# Power-board-new-version.net
KiCad netlist of a schematic drawn in EAGLE
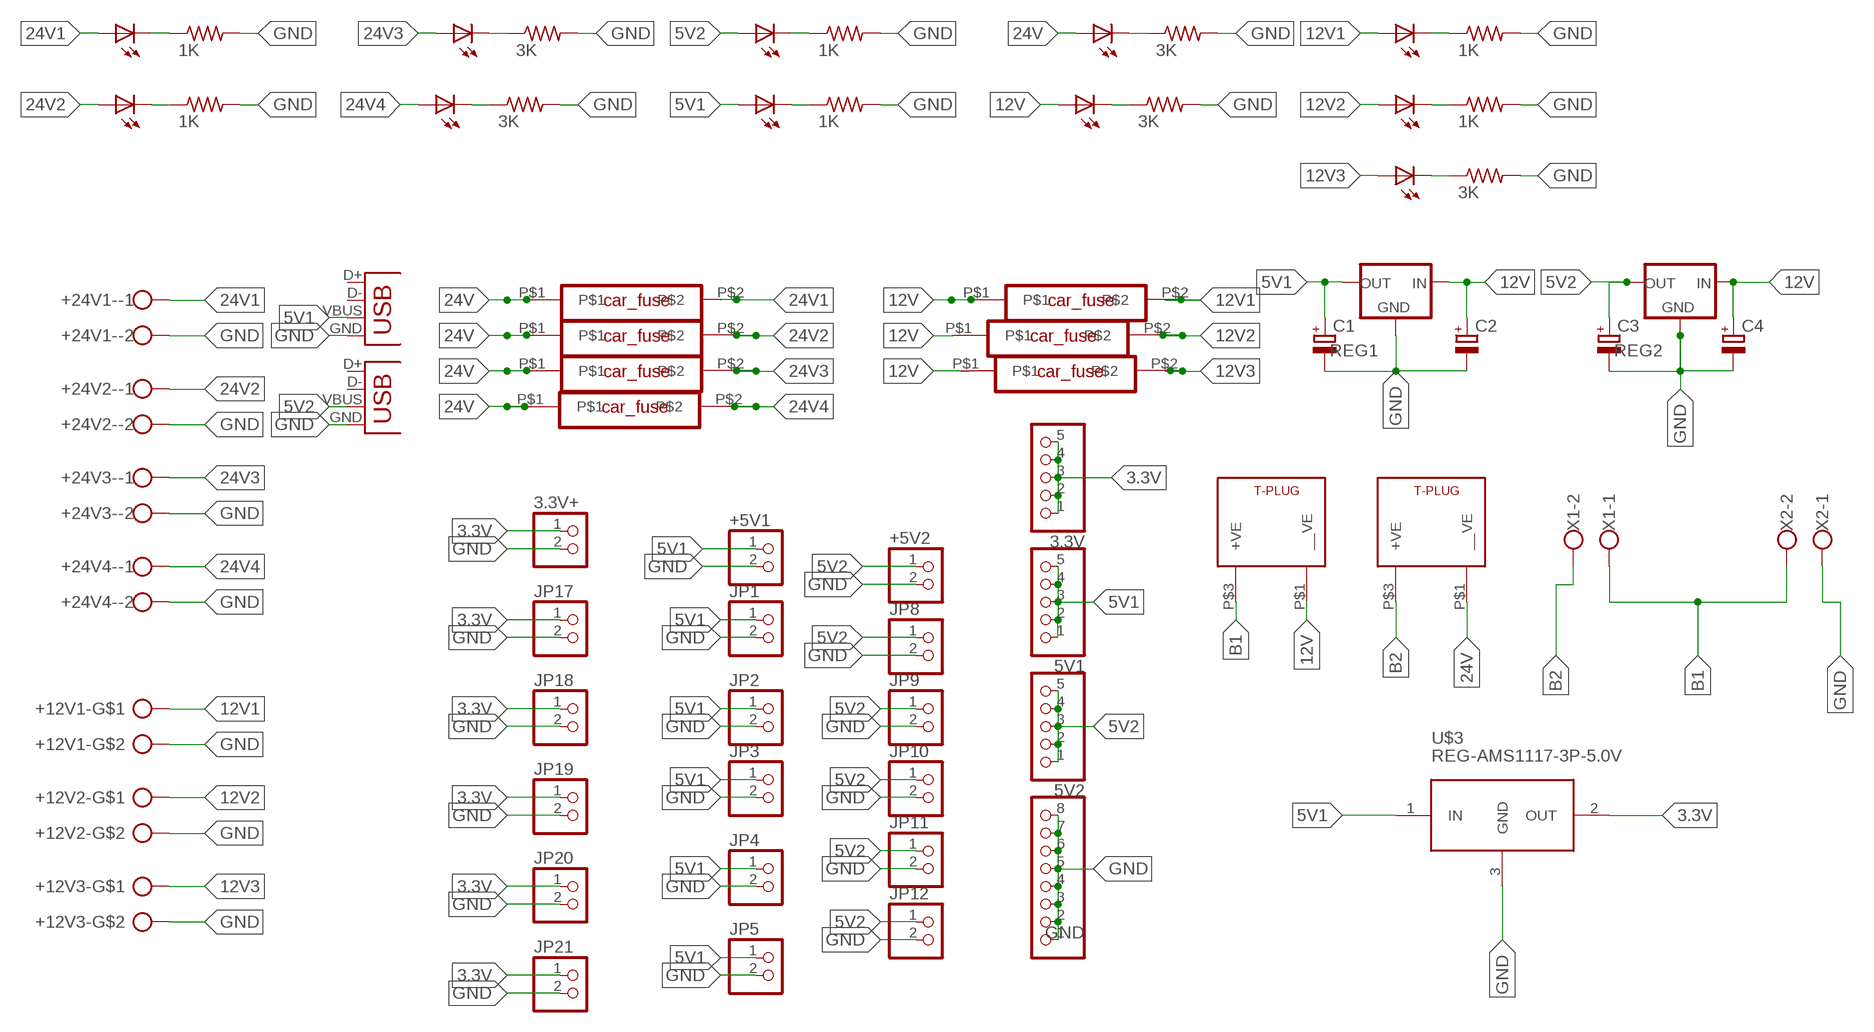
[diagram p0: schematic, sheet 1]

(export (version "E")
  (design (tool "Eeschema 10.0.6"))
  (components
    (comp (ref "+5V1")
      (value "PINHD-2_DATA")
      (footprint "eagle-import:1X02_DATA")
      (libsource (lib "eagle-import") (part "PINHD-2_DATA"))
    )
    (comp (ref "+5V2")
      (value "PINHD-2_DATA")
      (footprint "eagle-import:1X02_DATA")
      (libsource (lib "eagle-import") (part "PINHD-2_DATA"))
    )
    (comp (ref "+12V1-")
      (value "CON_PTR_2")
      (footprint "eagle-import:AK300_2")
      (libsource (lib "eagle-import") (part "CON_PTR_2"))
    )
    (comp (ref "+12V2-")
      (value "CON_PTR_2")
      (footprint "eagle-import:AK300_2")
      (libsource (lib "eagle-import") (part "CON_PTR_2"))
    )
    (comp (ref "+12V3-")
      (value "CON_PTR_2")
      (footprint "eagle-import:AK300_2")
      (libsource (lib "eagle-import") (part "CON_PTR_2"))
    )
    (comp (ref "+24V1-")
      (value "ROSTA.POWER")
      (footprint "eagle-import:W239-302")
      (libsource (lib "eagle-import") (part "ROSTA.POWER"))
    )
    (comp (ref "+24V2-")
      (value "ROSTA.POWER")
      (footprint "eagle-import:W239-302")
      (libsource (lib "eagle-import") (part "ROSTA.POWER"))
    )
    (comp (ref "+24V3-")
      (value "ROSTA.POWER")
      (footprint "eagle-import:W239-302")
      (libsource (lib "eagle-import") (part "ROSTA.POWER"))
    )
    (comp (ref "+24V4-")
      (value "ROSTA.POWER")
      (footprint "eagle-import:W239-302")
      (libsource (lib "eagle-import") (part "ROSTA.POWER"))
    )
    (comp (ref "1K")
      (value "1K")
      (footprint "eagle-import:0204_7")
      (libsource (lib "eagle-import") (part "RES-7"))
    )
    (comp (ref "1K1")
      (value "1K")
      (footprint "eagle-import:0204_7")
      (libsource (lib "eagle-import") (part "RES-7"))
    )
    (comp (ref "1K2")
      (value "1K")
      (footprint "eagle-import:0204_7")
      (libsource (lib "eagle-import") (part "RES-7"))
    )
    (comp (ref "3.3V")
      (value "PINHD-1X5")
      (footprint "eagle-import:1X05")
      (libsource (lib "eagle-import") (part "PINHD-1X5"))
    )
    (comp (ref "3.3V+")
      (value "PINHD-2_DATA")
      (footprint "eagle-import:1X02_DATA")
      (libsource (lib "eagle-import") (part "PINHD-2_DATA"))
    )
    (comp (ref "5V1")
      (value "PINHD-1X5")
      (footprint "eagle-import:1X05")
      (libsource (lib "eagle-import") (part "PINHD-1X5"))
    )
    (comp (ref "5V2")
      (value "PINHD-1X5")
      (footprint "eagle-import:1X05")
      (libsource (lib "eagle-import") (part "PINHD-1X5"))
    )
    (comp (ref "C1")
      (value "CAP_POL")
      (footprint "eagle-import:E3,5-8")
      (libsource (lib "eagle-import") (part "CAP_POL"))
    )
    (comp (ref "C2")
      (value "CAP_POL")
      (footprint "eagle-import:E3,5-8")
      (libsource (lib "eagle-import") (part "CAP_POL"))
    )
    (comp (ref "C3")
      (value "CAP_POL")
      (footprint "eagle-import:E3,5-8")
      (libsource (lib "eagle-import") (part "CAP_POL"))
    )
    (comp (ref "C4")
      (value "CAP_POL")
      (footprint "eagle-import:E3,5-8")
      (libsource (lib "eagle-import") (part "CAP_POL"))
    )
    (comp (ref "GND")
      (value "PINHD-1X8")
      (footprint "eagle-import:1X08")
      (libsource (lib "eagle-import") (part "PINHD-1X8"))
    )
    (comp (ref "JP1")
      (value "PINHD-2_DATA")
      (footprint "eagle-import:1X02_DATA")
      (libsource (lib "eagle-import") (part "PINHD-2_DATA"))
    )
    (comp (ref "JP2")
      (value "PINHD-2_DATA")
      (footprint "eagle-import:1X02_DATA")
      (libsource (lib "eagle-import") (part "PINHD-2_DATA"))
    )
    (comp (ref "JP3")
      (value "PINHD-2_DATA")
      (footprint "eagle-import:1X02_DATA")
      (libsource (lib "eagle-import") (part "PINHD-2_DATA"))
    )
    (comp (ref "JP4")
      (value "PINHD-2_DATA")
      (footprint "eagle-import:1X02_DATA")
      (libsource (lib "eagle-import") (part "PINHD-2_DATA"))
    )
    (comp (ref "JP5")
      (value "PINHD-2_DATA")
      (footprint "eagle-import:1X02_DATA")
      (libsource (lib "eagle-import") (part "PINHD-2_DATA"))
    )
    (comp (ref "JP8")
      (value "PINHD-2_DATA")
      (footprint "eagle-import:1X02_DATA")
      (libsource (lib "eagle-import") (part "PINHD-2_DATA"))
    )
    (comp (ref "JP9")
      (value "PINHD-2_DATA")
      (footprint "eagle-import:1X02_DATA")
      (libsource (lib "eagle-import") (part "PINHD-2_DATA"))
    )
    (comp (ref "JP10")
      (value "PINHD-2_DATA")
      (footprint "eagle-import:1X02_DATA")
      (libsource (lib "eagle-import") (part "PINHD-2_DATA"))
    )
    (comp (ref "JP11")
      (value "PINHD-2_DATA")
      (footprint "eagle-import:1X02_DATA")
      (libsource (lib "eagle-import") (part "PINHD-2_DATA"))
    )
    (comp (ref "JP12")
      (value "PINHD-2_DATA")
      (footprint "eagle-import:1X02_DATA")
      (libsource (lib "eagle-import") (part "PINHD-2_DATA"))
    )
    (comp (ref "JP17")
      (value "PINHD-2_DATA")
      (footprint "eagle-import:1X02_DATA")
      (libsource (lib "eagle-import") (part "PINHD-2_DATA"))
    )
    (comp (ref "JP18")
      (value "PINHD-2_DATA")
      (footprint "eagle-import:1X02_DATA")
      (libsource (lib "eagle-import") (part "PINHD-2_DATA"))
    )
    (comp (ref "JP19")
      (value "PINHD-2_DATA")
      (footprint "eagle-import:1X02_DATA")
      (libsource (lib "eagle-import") (part "PINHD-2_DATA"))
    )
    (comp (ref "JP20")
      (value "PINHD-2_DATA")
      (footprint "eagle-import:1X02_DATA")
      (libsource (lib "eagle-import") (part "PINHD-2_DATA"))
    )
    (comp (ref "JP21")
      (value "PINHD-2_DATA")
      (footprint "eagle-import:1X02_DATA")
      (libsource (lib "eagle-import") (part "PINHD-2_DATA"))
    )
    (comp (ref "REG1")
      (value "78XX-METAL")
      (footprint "eagle-import:TO3-79")
      (libsource (lib "eagle-import") (part "78XX-METAL"))
    )
    (comp (ref "REG2")
      (value "78XX-METAL")
      (footprint "eagle-import:TO3-79")
      (libsource (lib "eagle-import") (part "78XX-METAL"))
    )
    (comp (ref "U$1")
      (value "LED5V2")
      (footprint "eagle-import:LED3MM")
      (libsource (lib "eagle-import") (part "LED3MM"))
    )
    (comp (ref "U$2")
      (value "LED5V1")
      (footprint "eagle-import:LED3MM")
      (libsource (lib "eagle-import") (part "LED3MM"))
    )
    (comp (ref "U$3")
      (value "REG-AMS1117-3P-5.0V")
      (footprint "eagle-import:REG-AMS1117-3P")
      (libsource (lib "eagle-import") (part "REG-AMS1117-3P-5.0V"))
    )
    (comp (ref "U$4")
      (value "LED24V")
      (footprint "eagle-import:LED3MM")
      (libsource (lib "eagle-import") (part "LED3MM"))
    )
    (comp (ref "U$5")
      (value "T_CONNECTOR")
      (footprint "eagle-import:T-PLUG")
      (libsource (lib "eagle-import") (part "T_CONNECTOR"))
    )
    (comp (ref "U$6")
      (value "T_CONNECTOR")
      (footprint "eagle-import:T-PLUG")
      (libsource (lib "eagle-import") (part "T_CONNECTOR"))
    )
    (comp (ref "U$7")
      (value "1K")
      (footprint "eagle-import:0204_7")
      (libsource (lib "eagle-import") (part "RES-7"))
    )
    (comp (ref "U$8")
      (value "3K")
      (footprint "eagle-import:0204_7")
      (libsource (lib "eagle-import") (part "RES-7"))
    )
    (comp (ref "U$9")
      (value "3K")
      (footprint "eagle-import:0204_7")
      (libsource (lib "eagle-import") (part "RES-7"))
    )
    (comp (ref "U$10")
      (value "CAR_FUSE")
      (footprint "eagle-import:CAR_FUSE")
      (libsource (lib "eagle-import") (part "CAR_FUSE"))
    )
    (comp (ref "U$11")
      (value "CAR_FUSE")
      (footprint "eagle-import:CAR_FUSE")
      (libsource (lib "eagle-import") (part "CAR_FUSE"))
    )
    (comp (ref "U$12")
      (value "CAR_FUSE")
      (footprint "eagle-import:CAR_FUSE")
      (libsource (lib "eagle-import") (part "CAR_FUSE"))
    )
    (comp (ref "U$13")
      (value "CAR_FUSE")
      (footprint "eagle-import:CAR_FUSE")
      (libsource (lib "eagle-import") (part "CAR_FUSE"))
    )
    (comp (ref "U$14")
      (value "CAR_FUSE")
      (footprint "eagle-import:CAR_FUSE")
      (libsource (lib "eagle-import") (part "CAR_FUSE"))
    )
    (comp (ref "U$15")
      (value "CAR_FUSE")
      (footprint "eagle-import:CAR_FUSE")
      (libsource (lib "eagle-import") (part "CAR_FUSE"))
    )
    (comp (ref "U$16")
      (value "CAR_FUSE")
      (footprint "eagle-import:CAR_FUSE")
      (libsource (lib "eagle-import") (part "CAR_FUSE"))
    )
    (comp (ref "U$18")
      (value "LED5V2")
      (footprint "eagle-import:LED3MM")
      (libsource (lib "eagle-import") (part "LED3MM"))
    )
    (comp (ref "U$19")
      (value "LED5V1")
      (footprint "eagle-import:LED3MM")
      (libsource (lib "eagle-import") (part "LED3MM"))
    )
    (comp (ref "U$20")
      (value "LED24V")
      (footprint "eagle-import:LED3MM")
      (libsource (lib "eagle-import") (part "LED3MM"))
    )
    (comp (ref "U$21")
      (value "LED12V")
      (footprint "eagle-import:LED3MM")
      (libsource (lib "eagle-import") (part "LED3MM"))
    )
    (comp (ref "U$22")
      (value "1K")
      (footprint "eagle-import:0204_7")
      (libsource (lib "eagle-import") (part "RES-7"))
    )
    (comp (ref "U$23")
      (value "3K")
      (footprint "eagle-import:0204_7")
      (libsource (lib "eagle-import") (part "RES-7"))
    )
    (comp (ref "U$24")
      (value "3K")
      (footprint "eagle-import:0204_7")
      (libsource (lib "eagle-import") (part "RES-7"))
    )
    (comp (ref "U$25")
      (value "LED5V2")
      (footprint "eagle-import:LED3MM")
      (libsource (lib "eagle-import") (part "LED3MM"))
    )
    (comp (ref "U$26")
      (value "LED5V1")
      (footprint "eagle-import:LED3MM")
      (libsource (lib "eagle-import") (part "LED3MM"))
    )
    (comp (ref "U$27")
      (value "LED24V")
      (footprint "eagle-import:LED3MM")
      (libsource (lib "eagle-import") (part "LED3MM"))
    )
    (comp (ref "U$28")
      (value "LED24V")
      (footprint "eagle-import:LED3MM")
      (libsource (lib "eagle-import") (part "LED3MM"))
    )
    (comp (ref "U$29")
      (value "1K")
      (footprint "eagle-import:0204_7")
      (libsource (lib "eagle-import") (part "RES-7"))
    )
    (comp (ref "U$31")
      (value "3K")
      (footprint "eagle-import:0204_7")
      (libsource (lib "eagle-import") (part "RES-7"))
    )
    (comp (ref "USB1")
      (value "USB-A-H")
      (footprint "eagle-import:USB-A-H")
      (libsource (lib "eagle-import") (part "USB-A-H"))
    )
    (comp (ref "USB2")
      (value "USB-A-H")
      (footprint "eagle-import:USB-A-H")
      (libsource (lib "eagle-import") (part "USB-A-H"))
    )
    (comp (ref "X1")
      (value "ROSTA.POWER")
      (footprint "eagle-import:W239-302")
      (libsource (lib "eagle-import") (part "MIA_LIBRARY-2-2-2_16672108_ROSTA.POWER"))
    )
    (comp (ref "X2")
      (value "ROSTA.POWER")
      (footprint "eagle-import:W239-302")
      (libsource (lib "eagle-import") (part "MIA_LIBRARY-2-2-2_16672108_ROSTA.POWER"))
    )
  )
  (nets
    (net (code "1") (name "3.3V") (class "Default")
      (node (ref "3.3V") (pin "1") (pinfunction "1_1") (pintype "passive"))
      (node (ref "3.3V") (pin "2") (pinfunction "2_2") (pintype "passive"))
      (node (ref "3.3V") (pin "3") (pinfunction "3_3") (pintype "passive"))
      (node (ref "3.3V") (pin "4") (pinfunction "4_4") (pintype "passive"))
      (node (ref "3.3V") (pin "5") (pinfunction "5_5") (pintype "passive"))
      (node (ref "3.3V+") (pin "1") (pinfunction "1_1") (pintype "passive"))
      (node (ref "JP17") (pin "1") (pinfunction "1_1") (pintype "passive"))
      (node (ref "JP18") (pin "1") (pinfunction "1_1") (pintype "passive"))
      (node (ref "JP19") (pin "1") (pinfunction "1_1") (pintype "passive"))
      (node (ref "JP20") (pin "1") (pinfunction "1_1") (pintype "passive"))
      (node (ref "JP21") (pin "1") (pinfunction "1_1") (pintype "passive"))
      (node (ref "U$3") (pin "2") (pinfunction "OUT_2") (pintype "bidirectional"))
    )
    (net (code "2") (name "5V1") (class "Default")
      (node (ref "+5V1") (pin "1") (pinfunction "1_1") (pintype "passive"))
      (node (ref "5V1") (pin "1") (pinfunction "1_1") (pintype "passive"))
      (node (ref "5V1") (pin "2") (pinfunction "2_2") (pintype "passive"))
      (node (ref "5V1") (pin "3") (pinfunction "3_3") (pintype "passive"))
      (node (ref "5V1") (pin "4") (pinfunction "4_4") (pintype "passive"))
      (node (ref "5V1") (pin "5") (pinfunction "5_5") (pintype "passive"))
      (node (ref "C1") (pin "+") (pinfunction "+_+") (pintype "passive"))
      (node (ref "JP1") (pin "1") (pinfunction "1_1") (pintype "passive"))
      (node (ref "JP2") (pin "1") (pinfunction "1_1") (pintype "passive"))
      (node (ref "JP3") (pin "1") (pinfunction "1_1") (pintype "passive"))
      (node (ref "JP4") (pin "1") (pinfunction "1_1") (pintype "passive"))
      (node (ref "JP5") (pin "1") (pinfunction "1_1") (pintype "passive"))
      (node (ref "REG1") (pin "1") (pinfunction "OUT_1") (pintype "passive"))
      (node (ref "U$2") (pin "A") (pinfunction "A_A") (pintype "passive"))
      (node (ref "U$3") (pin "1") (pinfunction "IN_1") (pintype "bidirectional"))
      (node (ref "USB1") (pin "VBUS") (pinfunction "VBUS_VBUS") (pintype "bidirectional"))
    )
    (net (code "3") (name "5V2") (class "Default")
      (node (ref "+5V2") (pin "1") (pinfunction "1_1") (pintype "passive"))
      (node (ref "5V2") (pin "1") (pinfunction "1_1") (pintype "passive"))
      (node (ref "5V2") (pin "2") (pinfunction "2_2") (pintype "passive"))
      (node (ref "5V2") (pin "3") (pinfunction "3_3") (pintype "passive"))
      (node (ref "5V2") (pin "4") (pinfunction "4_4") (pintype "passive"))
      (node (ref "5V2") (pin "5") (pinfunction "5_5") (pintype "passive"))
      (node (ref "C3") (pin "+") (pinfunction "+_+") (pintype "passive"))
      (node (ref "JP10") (pin "1") (pinfunction "1_1") (pintype "passive"))
      (node (ref "JP11") (pin "1") (pinfunction "1_1") (pintype "passive"))
      (node (ref "JP12") (pin "1") (pinfunction "1_1") (pintype "passive"))
      (node (ref "JP8") (pin "1") (pinfunction "1_1") (pintype "passive"))
      (node (ref "JP9") (pin "1") (pinfunction "1_1") (pintype "passive"))
      (node (ref "REG2") (pin "1") (pinfunction "OUT_1") (pintype "passive"))
      (node (ref "U$1") (pin "A") (pinfunction "A_A") (pintype "passive"))
      (node (ref "USB2") (pin "VBUS") (pinfunction "VBUS_VBUS") (pintype "bidirectional"))
    )
    (net (code "4") (name "12V") (class "Default")
      (node (ref "C2") (pin "+") (pinfunction "+_+") (pintype "passive"))
      (node (ref "C4") (pin "+") (pinfunction "+_+") (pintype "passive"))
      (node (ref "REG1") (pin "3") (pinfunction "IN_3") (pintype "input"))
      (node (ref "REG2") (pin "3") (pinfunction "IN_3") (pintype "input"))
      (node (ref "U$14") (pin "P$1") (pinfunction "P$1_P$1") (pintype "bidirectional"))
      (node (ref "U$15") (pin "P$1") (pinfunction "P$1_P$1") (pintype "bidirectional"))
      (node (ref "U$16") (pin "P$1") (pinfunction "P$1_P$1") (pintype "bidirectional"))
      (node (ref "U$28") (pin "A") (pinfunction "A_A") (pintype "passive"))
      (node (ref "U$5") (pin "P$1") (pinfunction "__VE_P$1") (pintype "bidirectional"))
    )
    (net (code "5") (name "12V1") (class "Default")
      (node (ref "+12V1-") (pin "1") (pinfunction "KL_1") (pintype "passive"))
      (node (ref "U$14") (pin "P$2") (pinfunction "P$2_P$2") (pintype "bidirectional"))
      (node (ref "U$25") (pin "A") (pinfunction "A_A") (pintype "passive"))
    )
    (net (code "6") (name "12V2") (class "Default")
      (node (ref "+12V2-") (pin "1") (pinfunction "KL_1") (pintype "passive"))
      (node (ref "U$15") (pin "P$2") (pinfunction "P$2_P$2") (pintype "bidirectional"))
      (node (ref "U$26") (pin "A") (pinfunction "A_A") (pintype "passive"))
    )
    (net (code "7") (name "12V3") (class "Default")
      (node (ref "+12V3-") (pin "1") (pinfunction "KL_1") (pintype "passive"))
      (node (ref "U$16") (pin "P$2") (pinfunction "P$2_P$2") (pintype "bidirectional"))
      (node (ref "U$27") (pin "A") (pinfunction "A_A") (pintype "passive"))
    )
    (net (code "8") (name "24V") (class "Default")
      (node (ref "U$10") (pin "P$1") (pinfunction "P$1_P$1") (pintype "bidirectional"))
      (node (ref "U$11") (pin "P$1") (pinfunction "P$1_P$1") (pintype "bidirectional"))
      (node (ref "U$12") (pin "P$1") (pinfunction "P$1_P$1") (pintype "bidirectional"))
      (node (ref "U$13") (pin "P$1") (pinfunction "P$1_P$1") (pintype "bidirectional"))
      (node (ref "U$4") (pin "A") (pinfunction "A_A") (pintype "passive"))
      (node (ref "U$6") (pin "P$1") (pinfunction "__VE_P$1") (pintype "bidirectional"))
    )
    (net (code "9") (name "24V1") (class "Default")
      (node (ref "+24V1-") (pin "1") (pinfunction "KL_1") (pintype "passive"))
      (node (ref "U$10") (pin "P$2") (pinfunction "P$2_P$2") (pintype "bidirectional"))
      (node (ref "U$18") (pin "A") (pinfunction "A_A") (pintype "passive"))
    )
    (net (code "10") (name "24V2") (class "Default")
      (node (ref "+24V2-") (pin "1") (pinfunction "KL_1") (pintype "passive"))
      (node (ref "U$11") (pin "P$2") (pinfunction "P$2_P$2") (pintype "bidirectional"))
      (node (ref "U$19") (pin "A") (pinfunction "A_A") (pintype "passive"))
    )
    (net (code "11") (name "24V3") (class "Default")
      (node (ref "+24V3-") (pin "1") (pinfunction "KL_1") (pintype "passive"))
      (node (ref "U$12") (pin "P$2") (pinfunction "P$2_P$2") (pintype "bidirectional"))
      (node (ref "U$20") (pin "A") (pinfunction "A_A") (pintype "passive"))
    )
    (net (code "12") (name "24V4") (class "Default")
      (node (ref "+24V4-") (pin "1") (pinfunction "KL_1") (pintype "passive"))
      (node (ref "U$13") (pin "P$2") (pinfunction "P$2_P$2") (pintype "bidirectional"))
      (node (ref "U$21") (pin "A") (pinfunction "A_A") (pintype "passive"))
    )
    (net (code "13") (name "B1") (class "Default")
      (node (ref "U$5") (pin "P$3") (pinfunction "+VE_P$3") (pintype "bidirectional"))
      (node (ref "X1") (pin "1") (pinfunction "KL_1") (pintype "passive"))
      (node (ref "X2") (pin "2") (pinfunction "KL_2") (pintype "passive"))
    )
    (net (code "14") (name "B2") (class "Default")
      (node (ref "U$6") (pin "P$3") (pinfunction "+VE_P$3") (pintype "bidirectional"))
      (node (ref "X1") (pin "2") (pinfunction "KL_2") (pintype "passive"))
    )
    (net (code "15") (name "GND") (class "Default")
      (node (ref "+12V1-") (pin "2") (pinfunction "KL_2") (pintype "passive"))
      (node (ref "+12V2-") (pin "2") (pinfunction "KL_2") (pintype "passive"))
      (node (ref "+12V3-") (pin "2") (pinfunction "KL_2") (pintype "passive"))
      (node (ref "+24V1-") (pin "2") (pinfunction "KL_2") (pintype "passive"))
      (node (ref "+24V2-") (pin "2") (pinfunction "KL_2") (pintype "passive"))
      (node (ref "+24V3-") (pin "2") (pinfunction "KL_2") (pintype "passive"))
      (node (ref "+24V4-") (pin "2") (pinfunction "KL_2") (pintype "passive"))
      (node (ref "+5V1") (pin "2") (pinfunction "2_2") (pintype "passive"))
      (node (ref "+5V2") (pin "2") (pinfunction "2_2") (pintype "passive"))
      (node (ref "1K") (pin "2") (pinfunction "2_2") (pintype "passive"))
      (node (ref "1K1") (pin "2") (pinfunction "2_2") (pintype "passive"))
      (node (ref "1K2") (pin "2") (pinfunction "2_2") (pintype "passive"))
      (node (ref "3.3V+") (pin "2") (pinfunction "2_2") (pintype "passive"))
      (node (ref "C1") (pin "-") (pinfunction "-_-") (pintype "passive"))
      (node (ref "C2") (pin "-") (pinfunction "-_-") (pintype "passive"))
      (node (ref "C3") (pin "-") (pinfunction "-_-") (pintype "passive"))
      (node (ref "C4") (pin "-") (pinfunction "-_-") (pintype "passive"))
      (node (ref "GND") (pin "1") (pinfunction "1_1") (pintype "passive"))
      (node (ref "GND") (pin "2") (pinfunction "2_2") (pintype "passive"))
      (node (ref "GND") (pin "3") (pinfunction "3_3") (pintype "passive"))
      (node (ref "GND") (pin "4") (pinfunction "4_4") (pintype "passive"))
      (node (ref "GND") (pin "5") (pinfunction "5_5") (pintype "passive"))
      (node (ref "GND") (pin "6") (pinfunction "6_6") (pintype "passive"))
      (node (ref "GND") (pin "7") (pinfunction "7_7") (pintype "passive"))
      (node (ref "GND") (pin "8") (pinfunction "8_8") (pintype "passive"))
      (node (ref "JP1") (pin "2") (pinfunction "2_2") (pintype "passive"))
      (node (ref "JP10") (pin "2") (pinfunction "2_2") (pintype "passive"))
      (node (ref "JP11") (pin "2") (pinfunction "2_2") (pintype "passive"))
      (node (ref "JP12") (pin "2") (pinfunction "2_2") (pintype "passive"))
      (node (ref "JP17") (pin "2") (pinfunction "2_2") (pintype "passive"))
      (node (ref "JP18") (pin "2") (pinfunction "2_2") (pintype "passive"))
      (node (ref "JP19") (pin "2") (pinfunction "2_2") (pintype "passive"))
      (node (ref "JP2") (pin "2") (pinfunction "2_2") (pintype "passive"))
      (node (ref "JP20") (pin "2") (pinfunction "2_2") (pintype "passive"))
      (node (ref "JP21") (pin "2") (pinfunction "2_2") (pintype "passive"))
      (node (ref "JP3") (pin "2") (pinfunction "2_2") (pintype "passive"))
      (node (ref "JP4") (pin "2") (pinfunction "2_2") (pintype "passive"))
      (node (ref "JP5") (pin "2") (pinfunction "2_2") (pintype "passive"))
      (node (ref "JP8") (pin "2") (pinfunction "2_2") (pintype "passive"))
      (node (ref "JP9") (pin "2") (pinfunction "2_2") (pintype "passive"))
      (node (ref "REG1") (pin "2") (pinfunction "GND_2") (pintype "input"))
      (node (ref "REG2") (pin "2") (pinfunction "GND_2") (pintype "input"))
      (node (ref "U$22") (pin "2") (pinfunction "2_2") (pintype "passive"))
      (node (ref "U$23") (pin "2") (pinfunction "2_2") (pintype "passive"))
      (node (ref "U$24") (pin "2") (pinfunction "2_2") (pintype "passive"))
      (node (ref "U$29") (pin "2") (pinfunction "2_2") (pintype "passive"))
      (node (ref "U$3") (pin "3") (pinfunction "GND_3") (pintype "bidirectional"))
      (node (ref "U$31") (pin "2") (pinfunction "2_2") (pintype "passive"))
      (node (ref "U$7") (pin "2") (pinfunction "2_2") (pintype "passive"))
      (node (ref "U$8") (pin "2") (pinfunction "2_2") (pintype "passive"))
      (node (ref "U$9") (pin "2") (pinfunction "2_2") (pintype "passive"))
      (node (ref "USB1") (pin "GND") (pinfunction "GND_GND") (pintype "bidirectional"))
      (node (ref "USB2") (pin "GND") (pinfunction "GND_GND") (pintype "bidirectional"))
      (node (ref "X2") (pin "1") (pinfunction "KL_1") (pintype "passive"))
    )
    (net (code "16") (name "Net-(U$1-C)") (class "Default")
      (node (ref "1K") (pin "1") (pinfunction "1_1") (pintype "passive"))
      (node (ref "U$1") (pin "K") (pinfunction "C_K") (pintype "passive"))
    )
    (net (code "17") (name "Net-(U$2-C)") (class "Default")
      (node (ref "U$2") (pin "K") (pinfunction "C_K") (pintype "passive"))
      (node (ref "U$7") (pin "1") (pinfunction "1_1") (pintype "passive"))
    )
    (net (code "18") (name "Net-(U$4-C)") (class "Default")
      (node (ref "U$4") (pin "K") (pinfunction "C_K") (pintype "passive"))
      (node (ref "U$9") (pin "1") (pinfunction "1_1") (pintype "passive"))
    )
    (net (code "19") (name "Net-(U$18-C)") (class "Default")
      (node (ref "1K1") (pin "1") (pinfunction "1_1") (pintype "passive"))
      (node (ref "U$18") (pin "K") (pinfunction "C_K") (pintype "passive"))
    )
    (net (code "20") (name "Net-(U$19-C)") (class "Default")
      (node (ref "U$19") (pin "K") (pinfunction "C_K") (pintype "passive"))
      (node (ref "U$22") (pin "1") (pinfunction "1_1") (pintype "passive"))
    )
    (net (code "21") (name "Net-(U$20-C)") (class "Default")
      (node (ref "U$20") (pin "K") (pinfunction "C_K") (pintype "passive"))
      (node (ref "U$24") (pin "1") (pinfunction "1_1") (pintype "passive"))
    )
    (net (code "22") (name "Net-(U$21-C)") (class "Default")
      (node (ref "U$21") (pin "K") (pinfunction "C_K") (pintype "passive"))
      (node (ref "U$23") (pin "1") (pinfunction "1_1") (pintype "passive"))
    )
    (net (code "23") (name "Net-(U$25-C)") (class "Default")
      (node (ref "1K2") (pin "1") (pinfunction "1_1") (pintype "passive"))
      (node (ref "U$25") (pin "K") (pinfunction "C_K") (pintype "passive"))
    )
    (net (code "24") (name "Net-(U$26-C)") (class "Default")
      (node (ref "U$26") (pin "K") (pinfunction "C_K") (pintype "passive"))
      (node (ref "U$29") (pin "1") (pinfunction "1_1") (pintype "passive"))
    )
    (net (code "25") (name "Net-(U$27-C)") (class "Default")
      (node (ref "U$27") (pin "K") (pinfunction "C_K") (pintype "passive"))
      (node (ref "U$31") (pin "1") (pinfunction "1_1") (pintype "passive"))
    )
    (net (code "26") (name "Net-(U$28-C)") (class "Default")
      (node (ref "U$28") (pin "K") (pinfunction "C_K") (pintype "passive"))
      (node (ref "U$8") (pin "1") (pinfunction "1_1") (pintype "passive"))
    )
    (net (code "27") (name "unconnected-(USB1-PadD+)") (class "Default")
      (node (ref "USB1") (pin "D+") (pinfunction "D+_D+") (pintype "bidirectional"))
    )
    (net (code "28") (name "unconnected-(USB1-PadD-)") (class "Default")
      (node (ref "USB1") (pin "D-") (pinfunction "D-_D-") (pintype "bidirectional"))
    )
    (net (code "29") (name "unconnected-(USB2-PadD+)") (class "Default")
      (node (ref "USB2") (pin "D+") (pinfunction "D+_D+") (pintype "bidirectional"))
    )
    (net (code "30") (name "unconnected-(USB2-PadD-)") (class "Default")
      (node (ref "USB2") (pin "D-") (pinfunction "D-_D-") (pintype "bidirectional"))
    )
  )
)
